# SCH_IOT-SMART-IRRIGATION-SYSTEM_2025-08-.net
KiCad netlist of a schematic drawn in EasyEDA
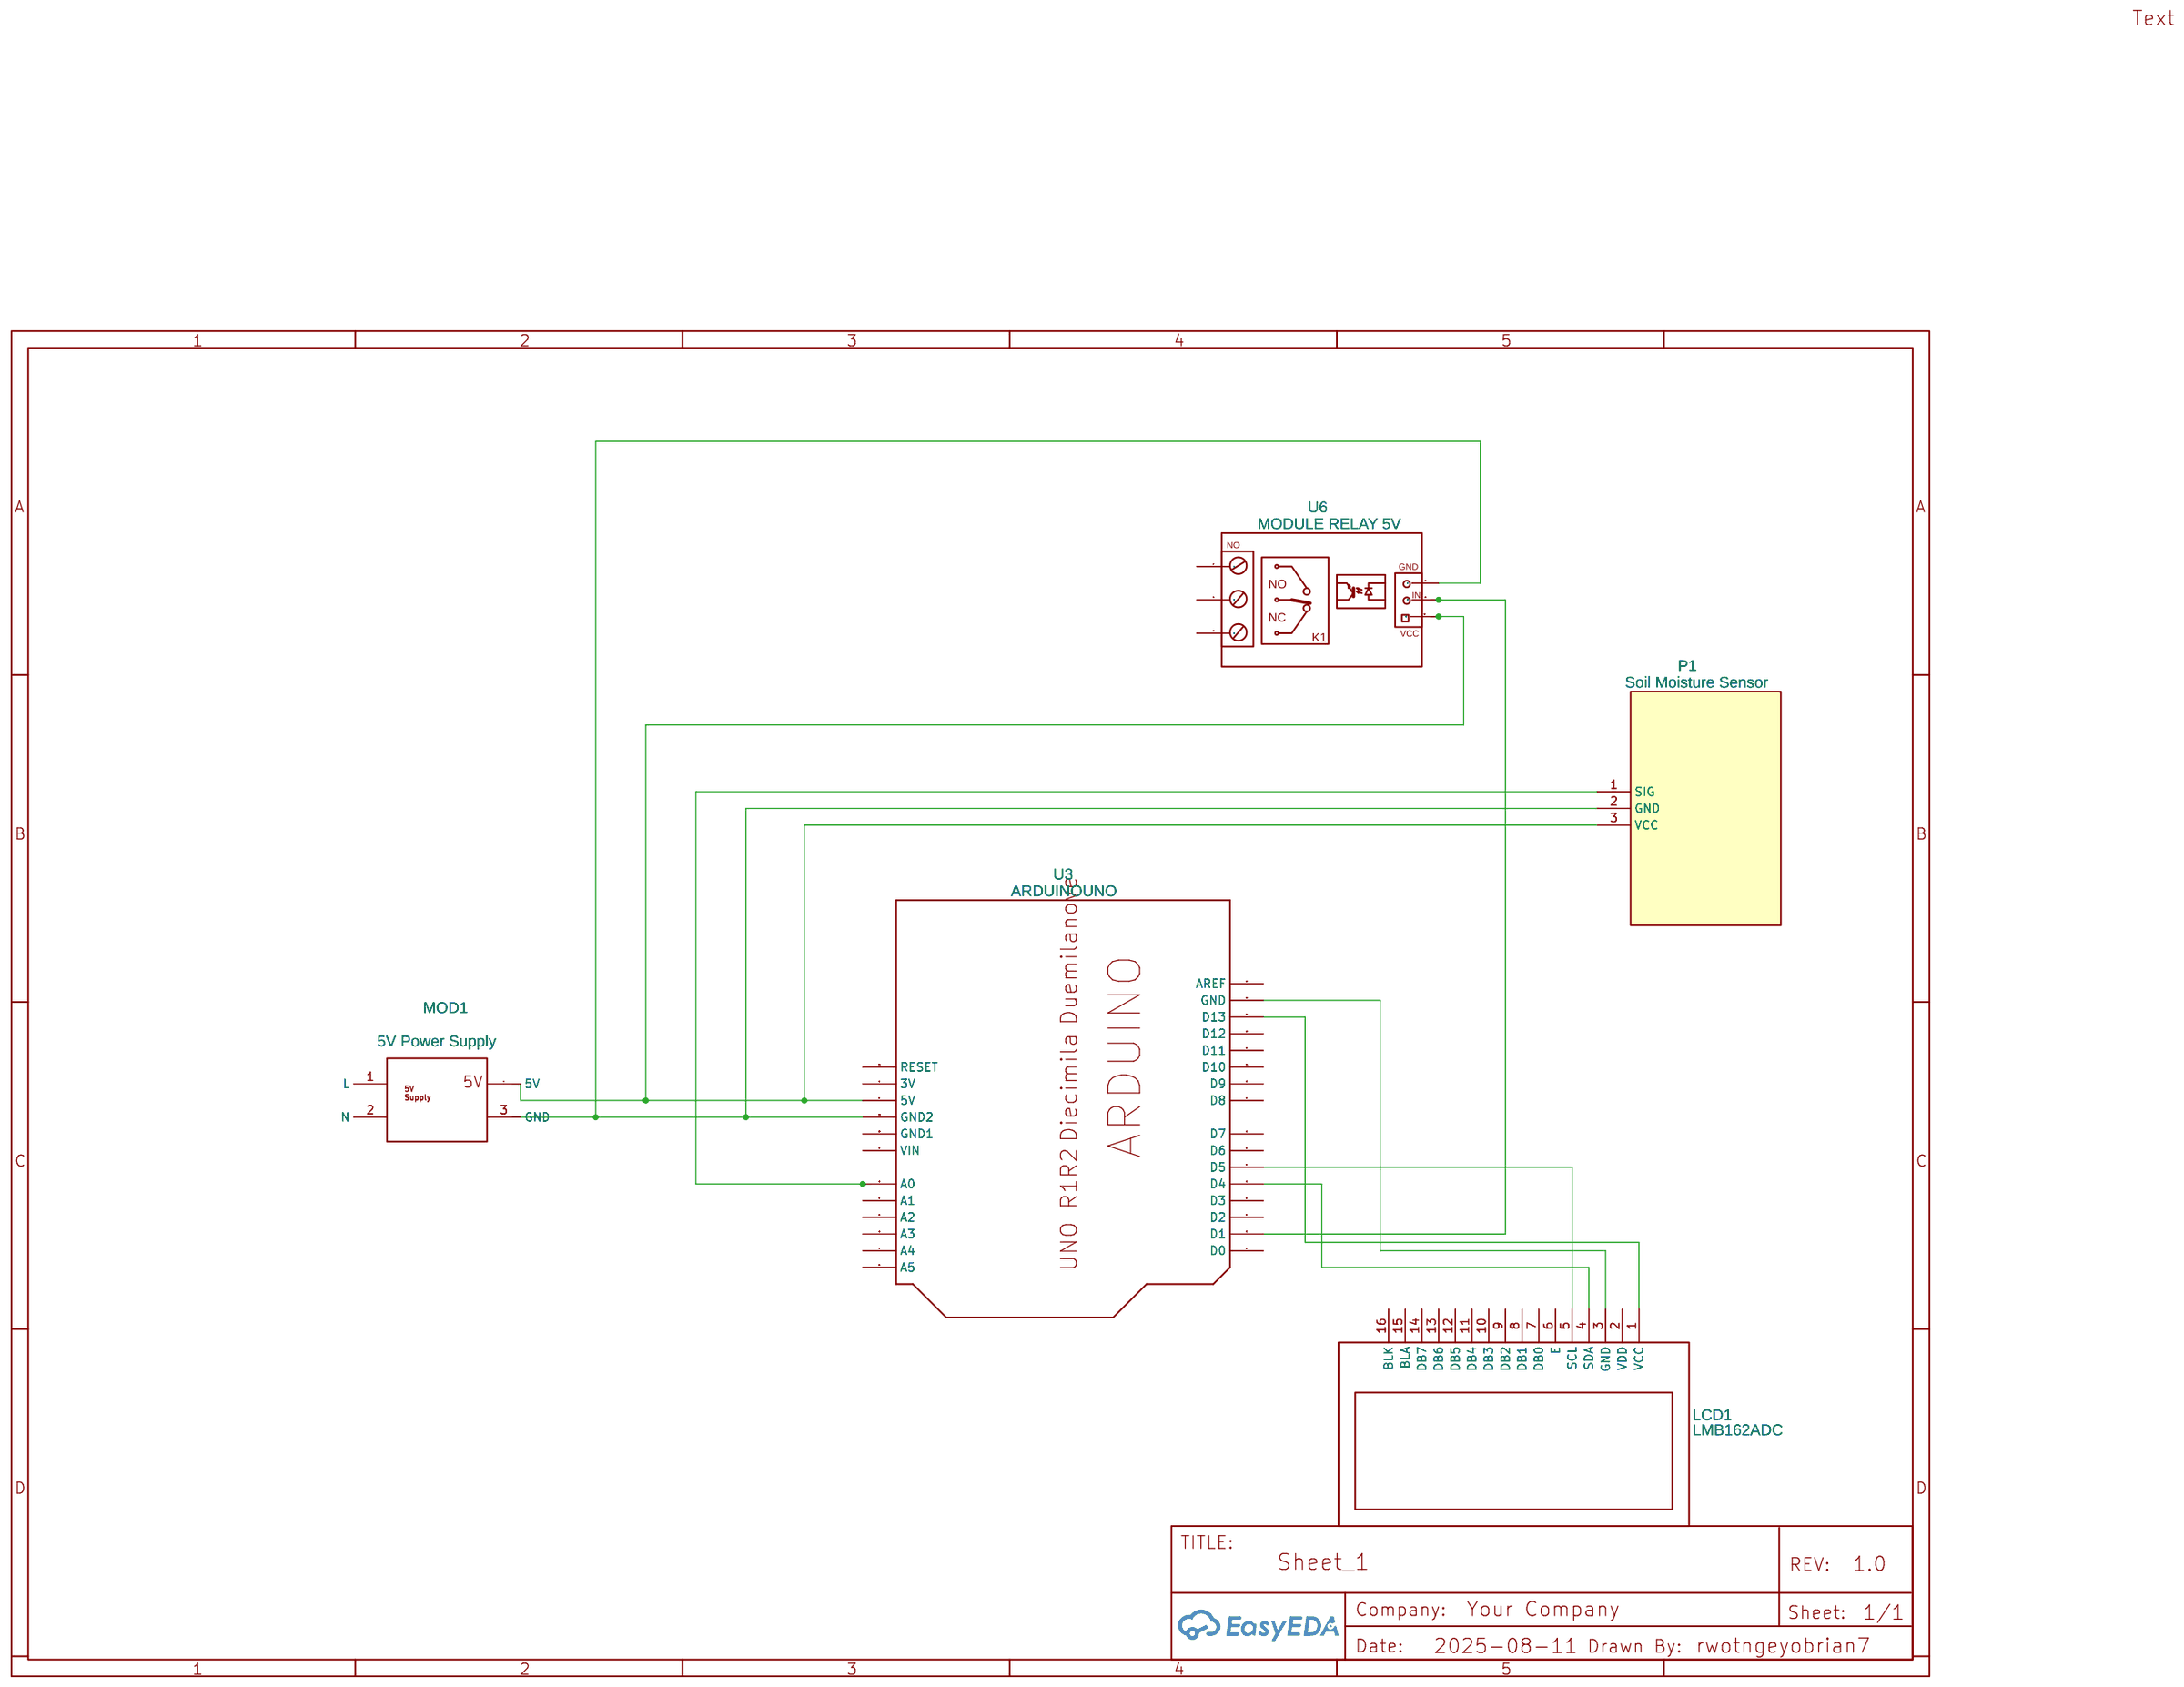
[diagram p0: schematic sheet]

(export (version "E")
  (design (tool "Eeschema 10.0.6"))
  (components
    (comp (ref "LCD1")
      (value "LMB162ADC")
      (fields (field (name "Manufacturer") "TOPWAY"))
      (libsource (lib "") (part "LMB162ADC"))
    )
    (comp (ref "MOD1") (value "5V Power Supply") (libsource (lib "") (part "5V Power Supply")))
    (comp (ref "P1") (value "Soil Moisture Sensor") (libsource (lib "") (part "Soil Moisture Sensor")))
    (comp (ref "U3") (value "ARDUINOUNO") (libsource (lib "") (part "ARDUINOUNO")))
    (comp (ref "U6")
      (value "MODULE RELAY 5V")
      (fields (field (name "Manufacturer Part") "1-Channel 5V Relay Module w/ Opto-isolator"))
      (libsource (lib "") (part "MODULE RELAY 5V"))
    )
  )
  (nets
    (net (code "1") (name "Net-(LCD1-GND)") (class "Default")
      (node (ref "LCD1") (pin "3") (pinfunction "GND_3") (pintype "unspecified"))
      (node (ref "U3") (pin "GND") (pinfunction "GND_GND") (pintype "passive"))
    )
    (net (code "2") (name "Net-(LCD1-SCL)") (class "Default")
      (node (ref "LCD1") (pin "5") (pinfunction "SCL_5") (pintype "unspecified"))
      (node (ref "U3") (pin "D5") (pinfunction "D5_D5") (pintype "unspecified"))
    )
    (net (code "3") (name "Net-(LCD1-SDA)") (class "Default")
      (node (ref "LCD1") (pin "4") (pinfunction "SDA_4") (pintype "unspecified"))
      (node (ref "U3") (pin "D4") (pinfunction "D4_D4") (pintype "unspecified"))
    )
    (net (code "4") (name "Net-(LCD1-VCC)") (class "Default")
      (node (ref "LCD1") (pin "1") (pinfunction "VCC_1") (pintype "unspecified"))
      (node (ref "U3") (pin "D13") (pinfunction "D13_D13") (pintype "unspecified"))
    )
    (net (code "5") (name "Net-(P1-GND)") (class "Default")
      (node (ref "P1") (pin "2") (pinfunction "GND_2") (pintype "unspecified"))
      (node (ref "U3") (pin "GND2") (pinfunction "GND2_GND2") (pintype "passive"))
      (node (ref "U6") (pin "14") (pinfunction "14_14") (pintype "input"))
    )
    (net (code "6") (name "Net-(P1-SIG)") (class "Default")
      (node (ref "P1") (pin "1") (pinfunction "SIG_1") (pintype "unspecified"))
      (node (ref "U3") (pin "A0") (pinfunction "A0_A0") (pintype "unspecified"))
    )
    (net (code "7") (name "Net-(P1-VCC)") (class "Default")
      (node (ref "P1") (pin "3") (pinfunction "VCC_3") (pintype "unspecified"))
      (node (ref "U3") (pin "5V") (pinfunction "5V_5V") (pintype "passive"))
      (node (ref "U6") (pin "13") (pinfunction "13_13") (pintype "input"))
    )
    (net (code "8") (name "Net-(U3-PadD1)") (class "Default")
      (node (ref "U3") (pin "D1") (pinfunction "D1_D1") (pintype "unspecified"))
      (node (ref "U6") (pin "15") (pinfunction "15_15") (pintype "input"))
    )
    (net (code "9") (name "unconnected-(LCD1-BLA-Pad15)") (class "Default")
      (node (ref "LCD1") (pin "15") (pinfunction "BLA_15") (pintype "unspecified"))
    )
    (net (code "10") (name "unconnected-(LCD1-BLK-Pad16)") (class "Default")
      (node (ref "LCD1") (pin "16") (pinfunction "BLK_16") (pintype "unspecified"))
    )
    (net (code "11") (name "unconnected-(LCD1-DB0-Pad7)") (class "Default")
      (node (ref "LCD1") (pin "7") (pinfunction "DB0_7") (pintype "unspecified"))
    )
    (net (code "12") (name "unconnected-(LCD1-DB1-Pad8)") (class "Default")
      (node (ref "LCD1") (pin "8") (pinfunction "DB1_8") (pintype "unspecified"))
    )
    (net (code "13") (name "unconnected-(LCD1-DB2-Pad9)") (class "Default")
      (node (ref "LCD1") (pin "9") (pinfunction "DB2_9") (pintype "unspecified"))
    )
    (net (code "14") (name "unconnected-(LCD1-DB3-Pad10)") (class "Default")
      (node (ref "LCD1") (pin "10") (pinfunction "DB3_10") (pintype "unspecified"))
    )
    (net (code "15") (name "unconnected-(LCD1-DB4-Pad11)") (class "Default")
      (node (ref "LCD1") (pin "11") (pinfunction "DB4_11") (pintype "unspecified"))
    )
    (net (code "16") (name "unconnected-(LCD1-DB5-Pad12)") (class "Default")
      (node (ref "LCD1") (pin "12") (pinfunction "DB5_12") (pintype "unspecified"))
    )
    (net (code "17") (name "unconnected-(LCD1-DB6-Pad13)") (class "Default")
      (node (ref "LCD1") (pin "13") (pinfunction "DB6_13") (pintype "unspecified"))
    )
    (net (code "18") (name "unconnected-(LCD1-DB7-Pad14)") (class "Default")
      (node (ref "LCD1") (pin "14") (pinfunction "DB7_14") (pintype "unspecified"))
    )
    (net (code "19") (name "unconnected-(LCD1-E-Pad6)") (class "Default")
      (node (ref "LCD1") (pin "6") (pinfunction "E_6") (pintype "unspecified"))
    )
    (net (code "20") (name "unconnected-(LCD1-VDD-Pad2)") (class "Default")
      (node (ref "LCD1") (pin "2") (pinfunction "VDD_2") (pintype "unspecified"))
    )
    (net (code "21") (name "unconnected-(MOD1-5V-Pad4)") (class "Default")
      (node (ref "MOD1") (pin "4") (pinfunction "5V_4") (pintype "unspecified"))
    )
    (net (code "22") (name "unconnected-(MOD1-GND-Pad3)") (class "Default")
      (node (ref "MOD1") (pin "3") (pinfunction "GND_3") (pintype "unspecified"))
    )
    (net (code "23") (name "unconnected-(MOD1-L-Pad1)") (class "Default")
      (node (ref "MOD1") (pin "1") (pinfunction "L_1") (pintype "unspecified"))
    )
    (net (code "24") (name "unconnected-(MOD1-N-Pad2)") (class "Default")
      (node (ref "MOD1") (pin "2") (pinfunction "N_2") (pintype "unspecified"))
    )
    (net (code "25") (name "unconnected-(U3-Pad3V)") (class "Default")
      (node (ref "U3") (pin "3V") (pinfunction "3V_3V") (pintype "passive"))
    )
    (net (code "26") (name "unconnected-(U3-PadA1)") (class "Default")
      (node (ref "U3") (pin "A1") (pinfunction "A1_A1") (pintype "unspecified"))
    )
    (net (code "27") (name "unconnected-(U3-PadA2)") (class "Default")
      (node (ref "U3") (pin "A2") (pinfunction "A2_A2") (pintype "unspecified"))
    )
    (net (code "28") (name "unconnected-(U3-PadA3)") (class "Default")
      (node (ref "U3") (pin "A3") (pinfunction "A3_A3") (pintype "unspecified"))
    )
    (net (code "29") (name "unconnected-(U3-PadA4)") (class "Default")
      (node (ref "U3") (pin "A4") (pinfunction "A4_A4") (pintype "unspecified"))
    )
    (net (code "30") (name "unconnected-(U3-PadA5)") (class "Default")
      (node (ref "U3") (pin "A5") (pinfunction "A5_A5") (pintype "unspecified"))
    )
    (net (code "31") (name "unconnected-(U3-PadAREF)") (class "Default")
      (node (ref "U3") (pin "AREF") (pinfunction "AREF_AREF") (pintype "unspecified"))
    )
    (net (code "32") (name "unconnected-(U3-PadD0)") (class "Default")
      (node (ref "U3") (pin "D0") (pinfunction "D0_D0") (pintype "unspecified"))
    )
    (net (code "33") (name "unconnected-(U3-PadD2)") (class "Default")
      (node (ref "U3") (pin "D2") (pinfunction "D2_D2") (pintype "unspecified"))
    )
    (net (code "34") (name "unconnected-(U3-PadD3)") (class "Default")
      (node (ref "U3") (pin "D3") (pinfunction "D3_D3") (pintype "unspecified"))
    )
    (net (code "35") (name "unconnected-(U3-PadD6)") (class "Default")
      (node (ref "U3") (pin "D6") (pinfunction "D6_D6") (pintype "unspecified"))
    )
    (net (code "36") (name "unconnected-(U3-PadD7)") (class "Default")
      (node (ref "U3") (pin "D7") (pinfunction "D7_D7") (pintype "unspecified"))
    )
    (net (code "37") (name "unconnected-(U3-PadD8)") (class "Default")
      (node (ref "U3") (pin "D8") (pinfunction "D8_D8") (pintype "unspecified"))
    )
    (net (code "38") (name "unconnected-(U3-PadD9)") (class "Default")
      (node (ref "U3") (pin "D9") (pinfunction "D9_D9") (pintype "unspecified"))
    )
    (net (code "39") (name "unconnected-(U3-PadD10)") (class "Default")
      (node (ref "U3") (pin "D10") (pinfunction "D10_D10") (pintype "unspecified"))
    )
    (net (code "40") (name "unconnected-(U3-PadD11)") (class "Default")
      (node (ref "U3") (pin "D11") (pinfunction "D11_D11") (pintype "unspecified"))
    )
    (net (code "41") (name "unconnected-(U3-PadD12)") (class "Default")
      (node (ref "U3") (pin "D12") (pinfunction "D12_D12") (pintype "unspecified"))
    )
    (net (code "42") (name "unconnected-(U3-PadGND1)") (class "Default")
      (node (ref "U3") (pin "GND1") (pinfunction "GND1_GND1") (pintype "passive"))
    )
    (net (code "43") (name "unconnected-(U3-PadRESET)") (class "Default")
      (node (ref "U3") (pin "RESET") (pinfunction "RESET_RESET") (pintype "unspecified"))
    )
    (net (code "44") (name "unconnected-(U3-PadVIN)") (class "Default")
      (node (ref "U3") (pin "VIN") (pinfunction "VIN_VIN") (pintype "passive"))
    )
    (net (code "45") (name "unconnected-(U6-Pad1)") (class "Default")
      (node (ref "U6") (pin "1") (pinfunction "1_1") (pintype "unspecified"))
    )
    (net (code "46") (name "unconnected-(U6-Pad2)") (class "Default")
      (node (ref "U6") (pin "2") (pinfunction "2_2") (pintype "unspecified"))
    )
    (net (code "47") (name "unconnected-(U6-Pad3)") (class "Default")
      (node (ref "U6") (pin "3") (pinfunction "3_3") (pintype "unspecified"))
    )
  )
)
